# Schema_Proiect_v120.net
KiCad netlist of a schematic drawn in EAGLE
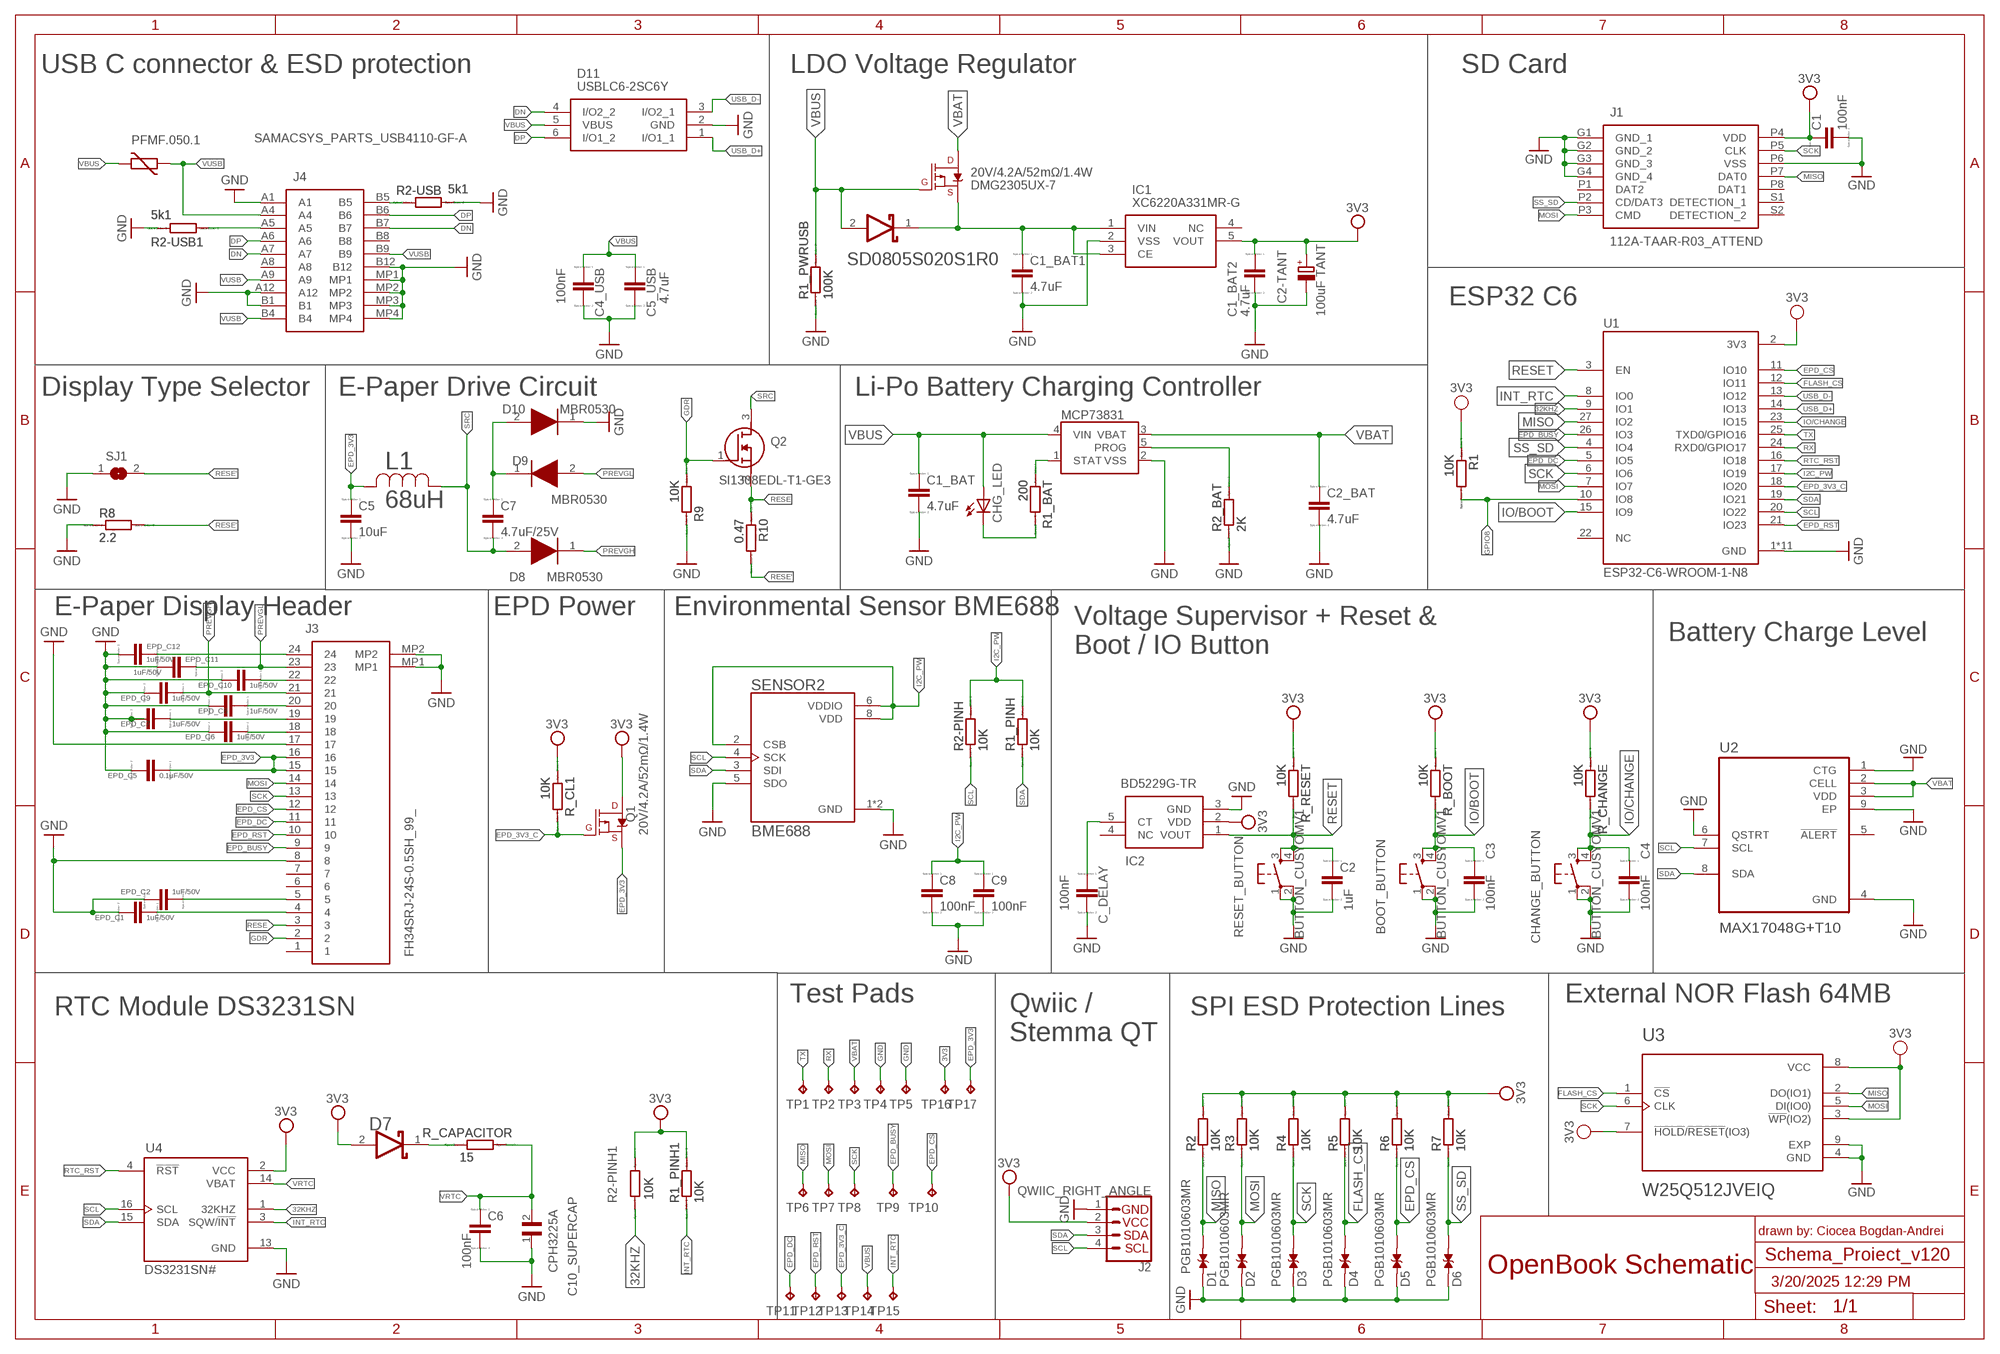
[diagram p0: schematic, sheet 1]

(export (version "E")
  (design (tool "Eeschema 10.0.6"))
  (components
    (comp (ref "BOOT_BUTTON")
      (value "BUTTON_CUSYOMV1")
      (footprint "eagle-import:MYBUTTON")
      (libsource (lib "eagle-import") (part "BUTTON_CUSYOMV1"))
    )
    (comp (ref "C1")
      (value "100nF")
      (footprint "eagle-import:EAGLE-LTSPICE_C0402")
      (libsource (lib "eagle-import") (part "EAGLE-LTSPICE_CC0402"))
    )
    (comp (ref "C1_BAT")
      (value "4.7uF")
      (footprint "eagle-import:EAGLE-LTSPICE_C0402")
      (libsource (lib "eagle-import") (part "EAGLE-LTSPICE_CC0402"))
    )
    (comp (ref "C1_BAT1")
      (value "4.7uF")
      (footprint "eagle-import:EAGLE-LTSPICE_C0402")
      (libsource (lib "eagle-import") (part "EAGLE-LTSPICE_CC0402"))
    )
    (comp (ref "C1_BAT2")
      (value "4.7uF")
      (footprint "eagle-import:EAGLE-LTSPICE_C0402")
      (libsource (lib "eagle-import") (part "EAGLE-LTSPICE_CC0402"))
    )
    (comp (ref "C2")
      (value "1uF")
      (footprint "eagle-import:EAGLE-LTSPICE_C0402")
      (libsource (lib "eagle-import") (part "EAGLE-LTSPICE_CC0402"))
    )
    (comp (ref "C2-TANT")
      (value "100uF TANT")
      (footprint "eagle-import:RCL_CT3528")
      (libsource (lib "eagle-import") (part "RCL_CPOL-EUCT3528"))
    )
    (comp (ref "C2_BAT")
      (value "4.7uF")
      (footprint "eagle-import:EAGLE-LTSPICE_C0402")
      (libsource (lib "eagle-import") (part "EAGLE-LTSPICE_CC0402"))
    )
    (comp (ref "C3")
      (value "100nF")
      (footprint "eagle-import:EAGLE-LTSPICE_C0402")
      (libsource (lib "eagle-import") (part "EAGLE-LTSPICE_CC0402"))
    )
    (comp (ref "C4")
      (value "100nF")
      (footprint "eagle-import:EAGLE-LTSPICE_C0402")
      (libsource (lib "eagle-import") (part "EAGLE-LTSPICE_CC0402"))
    )
    (comp (ref "C4_USB")
      (value "100nF")
      (footprint "eagle-import:EAGLE-LTSPICE_C0402")
      (libsource (lib "eagle-import") (part "EAGLE-LTSPICE_CC0402"))
    )
    (comp (ref "C5")
      (value "10uF")
      (footprint "eagle-import:EAGLE-LTSPICE_C0402")
      (libsource (lib "eagle-import") (part "EAGLE-LTSPICE_CC0402"))
    )
    (comp (ref "C5_USB")
      (value "4.7uF")
      (footprint "eagle-import:EAGLE-LTSPICE_C0402")
      (libsource (lib "eagle-import") (part "EAGLE-LTSPICE_CC0402"))
    )
    (comp (ref "C6")
      (value "100nF")
      (footprint "eagle-import:EAGLE-LTSPICE_C0402")
      (libsource (lib "eagle-import") (part "EAGLE-LTSPICE_CC0402"))
    )
    (comp (ref "C7")
      (value "4.7uF/25V")
      (footprint "eagle-import:EAGLE-LTSPICE_C0402")
      (libsource (lib "eagle-import") (part "EAGLE-LTSPICE_CC0402"))
    )
    (comp (ref "C8")
      (value "100nF")
      (footprint "eagle-import:EAGLE-LTSPICE_C0402")
      (libsource (lib "eagle-import") (part "EAGLE-LTSPICE_CC0402"))
    )
    (comp (ref "C9")
      (value "100nF")
      (footprint "eagle-import:EAGLE-LTSPICE_C0402")
      (libsource (lib "eagle-import") (part "EAGLE-LTSPICE_CC0402"))
    )
    (comp (ref "C10_SUPERCAP")
      (value "CPH3225A")
      (footprint "eagle-import:CAPCP3225X100N")
      (fields (field (name "MF") "Seiko Instruments"))
      (libsource (lib "eagle-import") (part "CPH3225A"))
    )
    (comp (ref "CHANGE_BUTTON")
      (value "BUTTON_CUSYOMV1")
      (footprint "eagle-import:MYBUTTON")
      (libsource (lib "eagle-import") (part "BUTTON_CUSYOMV1"))
    )
    (comp (ref "CHG_LED")
      (value "ADAFRUIT_LEDCHIP-LED0603")
      (footprint "eagle-import:ADAFRUIT_CHIP-LED0603")
      (libsource (lib "eagle-import") (part "ADAFRUIT_LEDCHIP-LED0603"))
    )
    (comp (ref "C_DELAY")
      (value "100nF")
      (footprint "eagle-import:EAGLE-LTSPICE_C0402")
      (libsource (lib "eagle-import") (part "EAGLE-LTSPICE_CC0402"))
    )
    (comp (ref "D1")
      (value "PGB1010603MR")
      (footprint "eagle-import:DIOC1608X36N")
      (fields (field (name "MF") "Littelfuse Inc."))
      (libsource (lib "eagle-import") (part "PGB1010603MR"))
    )
    (comp (ref "D2")
      (value "PGB1010603MR")
      (footprint "eagle-import:DIOC1608X36N")
      (fields (field (name "MF") "Littelfuse Inc."))
      (libsource (lib "eagle-import") (part "PGB1010603MR"))
    )
    (comp (ref "D3")
      (value "PGB1010603MR")
      (footprint "eagle-import:DIOC1608X36N")
      (fields (field (name "MF") "Littelfuse Inc."))
      (libsource (lib "eagle-import") (part "PGB1010603MR"))
    )
    (comp (ref "D4")
      (value "PGB1010603MR")
      (footprint "eagle-import:DIOC1608X36N")
      (fields (field (name "MF") "Littelfuse Inc."))
      (libsource (lib "eagle-import") (part "PGB1010603MR"))
    )
    (comp (ref "D5")
      (value "PGB1010603MR")
      (footprint "eagle-import:DIOC1608X36N")
      (fields (field (name "MF") "Littelfuse Inc."))
      (libsource (lib "eagle-import") (part "PGB1010603MR"))
    )
    (comp (ref "D6")
      (value "PGB1010603MR")
      (footprint "eagle-import:DIOC1608X36N")
      (fields (field (name "MF") "Littelfuse Inc."))
      (libsource (lib "eagle-import") (part "PGB1010603MR"))
    )
    (comp (ref "D7")
      (value "SD0805S020S1R0")
      (footprint "eagle-import:ESP32_WROVER_AVX---SD0805S020S1R0_AVX_SD0805S020S1R0_0")
      (fields
        (field (name "DIGIKEY_PART_NUMBER") "478-7800-1-ND")
        (field (name "MF") "AVX")
        (field (name "MOUSER_PART_NUMBER") "581-SD0805S020S1R0")
      )
      (libsource (lib "eagle-import") (part "ESP32_WROVER_AVX---SD0805S020S1R0_AVX_SD0805S020S1R0_0_0AVX_SD0805S020S1R0_0_0"))
    )
    (comp (ref "D8")
      (value "MBR0530")
      (footprint "eagle-import:SOD3716X135N")
      (fields (field (name "MF") "ON Semiconductor"))
      (libsource (lib "eagle-import") (part "MBR0530"))
    )
    (comp (ref "D9")
      (value "MBR0530")
      (footprint "eagle-import:SOD3716X135N")
      (fields (field (name "MF") "ON Semiconductor"))
      (libsource (lib "eagle-import") (part "MBR0530"))
    )
    (comp (ref "D10")
      (value "MBR0530")
      (footprint "eagle-import:SOD3716X135N")
      (fields (field (name "MF") "ON Semiconductor"))
      (libsource (lib "eagle-import") (part "MBR0530"))
    )
    (comp (ref "D11")
      (value "USBLC6-2SC6Y")
      (footprint "eagle-import:SOT95P280X145-6N")
      (fields (field (name "MF") "STMicroelectronics"))
      (libsource (lib "eagle-import") (part "USBLC6-2SC6Y"))
    )
    (comp (ref "DMG2305UX-7")
      (value "20V/4.2A/52mΩ/1.4W")
      (footprint "eagle-import:ESP32_WROVER_SPARKFUN-DISCRETESEMI_SOT23-3")
      (libsource (lib "eagle-import") (part "ESP32_WROVER_SPARKFUN-DISCRETESEMI_MOSFET_PCH-DMG2305UX-7"))
    )
    (comp (ref "EPD_C1")
      (value "1uF/50V")
      (footprint "eagle-import:EAGLE-LTSPICE_C0402")
      (libsource (lib "eagle-import") (part "EAGLE-LTSPICE_CC0402"))
    )
    (comp (ref "EPD_C2")
      (value "1uF/50V")
      (footprint "eagle-import:EAGLE-LTSPICE_C0402")
      (libsource (lib "eagle-import") (part "EAGLE-LTSPICE_CC0402"))
    )
    (comp (ref "EPD_C5")
      (value "0.1uF/50V")
      (footprint "eagle-import:EAGLE-LTSPICE_C0402")
      (libsource (lib "eagle-import") (part "EAGLE-LTSPICE_CC0402"))
    )
    (comp (ref "EPD_C6")
      (value "1uF/50V")
      (footprint "eagle-import:EAGLE-LTSPICE_C0402")
      (libsource (lib "eagle-import") (part "EAGLE-LTSPICE_CC0402"))
    )
    (comp (ref "EPD_C7")
      (value "1uF/50V")
      (footprint "eagle-import:EAGLE-LTSPICE_C0402")
      (libsource (lib "eagle-import") (part "EAGLE-LTSPICE_CC0402"))
    )
    (comp (ref "EPD_C8")
      (value "1uF/50V")
      (footprint "eagle-import:EAGLE-LTSPICE_C0402")
      (libsource (lib "eagle-import") (part "EAGLE-LTSPICE_CC0402"))
    )
    (comp (ref "EPD_C9")
      (value "1uF/50V")
      (footprint "eagle-import:EAGLE-LTSPICE_C0402")
      (libsource (lib "eagle-import") (part "EAGLE-LTSPICE_CC0402"))
    )
    (comp (ref "EPD_C10")
      (value "1uF/50V")
      (footprint "eagle-import:EAGLE-LTSPICE_C0402")
      (libsource (lib "eagle-import") (part "EAGLE-LTSPICE_CC0402"))
    )
    (comp (ref "EPD_C11")
      (value "1uF/50V")
      (footprint "eagle-import:EAGLE-LTSPICE_C0402")
      (libsource (lib "eagle-import") (part "EAGLE-LTSPICE_CC0402"))
    )
    (comp (ref "EPD_C12")
      (value "1uF/50V")
      (footprint "eagle-import:EAGLE-LTSPICE_C0402")
      (libsource (lib "eagle-import") (part "EAGLE-LTSPICE_CC0402"))
    )
    (comp (ref "IC1")
      (value "XC6220A331MR-G")
      (footprint "eagle-import:SOT95P280X120-5N")
      (fields (field (name "MOUSER_PART_NUMBER") "865-XC6220A331MR-G"))
      (libsource (lib "eagle-import") (part "XC6220A331MR-G"))
    )
    (comp (ref "IC2")
      (value "BD5229G-TR")
      (footprint "eagle-import:SOT95P280X125-5N")
      (fields (field (name "MOUSER_PART_NUMBER") "755-BD5229G-TR"))
      (libsource (lib "eagle-import") (part "BD5229G-TR"))
    )
    (comp (ref "J1")
      (value "112A-TAAR-R03_ATTEND")
      (footprint "eagle-import:112ATAARR03ATTEND")
      (fields (field (name "MANUFACTURER_PART_NUMBER") "112A-TAAR-R03 ATTEND"))
      (libsource (lib "eagle-import") (part "112A-TAAR-R03_ATTEND"))
    )
    (comp (ref "J2")
      (value "QWIIC_RIGHT_ANGLE")
      (footprint "eagle-import:JST04_1MM_RA")
      (libsource (lib "eagle-import") (part "QWIIC_CONNECTORJS-1MM"))
    )
    (comp (ref "J3")
      (value "FH34SRJ-24S-0.5SH_99_")
      (footprint "eagle-import:FH34SRJ24S05SH99")
      (fields
        (field (name "MANUFACTURER_PART_NUMBER") "FH34SRJ-24S-0.5SH(99)")
        (field (name "MOUSER_PART_NUMBER") "798-FH34SRJ24S05SH99")
      )
      (libsource (lib "eagle-import") (part "FH34SRJ-24S-0.5SH_99_"))
    )
    (comp (ref "J4")
      (value "SAMACSYS_PARTS_USB4110-GF-A")
      (footprint "eagle-import:SAMACSYS_PARTS_USB4110GFA")
      (fields
        (field (name "MANUFACTURER_PART_NUMBER") "USB4110-GF-A")
        (field (name "MOUSER_PART_NUMBER") "640-USB4110-GF-A")
      )
      (libsource (lib "eagle-import") (part "SAMACSYS_PARTS_USB4110-GF-A"))
    )
    (comp (ref "L1")
      (value "68uH")
      (footprint "eagle-import:IND_4828-WE-TPC_WRE")
      (fields
        (field (name "MANUFACTURER_PART_NUMBER") "744043680")
        (field (name "COPYRIGHT") "Copyright (C) 2024 Ultra Librarian. All rights reserved.")
      )
      (libsource (lib "eagle-import") (part "744043680IND_4828-WE-TPC_WRE"))
    )
    (comp (ref "MCP73831")
      (value "ESP32_WROVER_SPARKFUN-IC-POWER_MCP73831")
      (footprint "eagle-import:ESP32_WROVER_SPARKFUN-IC-POWER_SOT23-5")
      (libsource (lib "eagle-import") (part "ESP32_WROVER_SPARKFUN-IC-POWER_MCP73831"))
    )
    (comp (ref "PFMF.050.1")
      (value "ESP32C6_VARISTORCN1812")
      (footprint "eagle-import:ESP32C6_VARISTOR_CT_CN1812")
      (libsource (lib "eagle-import") (part "ESP32C6_VARISTORCN1812"))
    )
    (comp (ref "Q1")
      (value "20V/4.2A/52mΩ/1.4W")
      (footprint "eagle-import:ESP32_WROVER_SPARKFUN-DISCRETESEMI_SOT23-3")
      (libsource (lib "eagle-import") (part "ESP32_WROVER_SPARKFUN-DISCRETESEMI_MOSFET_PCH-DMG2305UX-7"))
    )
    (comp (ref "Q2")
      (value "SI1308EDL-T1-GE3")
      (footprint "eagle-import:SOT65P210X110-3N")
      (fields (field (name "MF") "Vishay Siliconix"))
      (libsource (lib "eagle-import") (part "SI1308EDL-T1-GE3"))
    )
    (comp (ref "R1")
      (value "10K")
      (footprint "eagle-import:ESP32_WROVER_EAGLE-LTSPICE_R0402")
      (libsource (lib "eagle-import") (part "ESP32_WROVER_EAGLE-LTSPICE_RR0402"))
    )
    (comp (ref "R1_BAT")
      (value "200")
      (footprint "eagle-import:ESP32_WROVER_EAGLE-LTSPICE_R0402")
      (libsource (lib "eagle-import") (part "ESP32_WROVER_EAGLE-LTSPICE_RR0402"))
    )
    (comp (ref "R1_PINH")
      (value "10K")
      (footprint "eagle-import:ESP32_WROVER_EAGLE-LTSPICE_R0402")
      (libsource (lib "eagle-import") (part "ESP32_WROVER_EAGLE-LTSPICE_RR0402"))
    )
    (comp (ref "R1_PINH1")
      (value "10K")
      (footprint "eagle-import:ESP32_WROVER_EAGLE-LTSPICE_R0402")
      (libsource (lib "eagle-import") (part "ESP32_WROVER_EAGLE-LTSPICE_RR0402"))
    )
    (comp (ref "R1_PWRUSB")
      (value "100K")
      (footprint "eagle-import:ESP32_WROVER_EAGLE-LTSPICE_R0402")
      (libsource (lib "eagle-import") (part "ESP32_WROVER_EAGLE-LTSPICE_RR0402"))
    )
    (comp (ref "R2")
      (value "10K")
      (footprint "eagle-import:ESP32_WROVER_EAGLE-LTSPICE_R0402")
      (libsource (lib "eagle-import") (part "ESP32_WROVER_EAGLE-LTSPICE_RR0402"))
    )
    (comp (ref "R2-PINH")
      (value "10K")
      (footprint "eagle-import:ESP32_WROVER_EAGLE-LTSPICE_R0402")
      (libsource (lib "eagle-import") (part "ESP32_WROVER_EAGLE-LTSPICE_RR0402"))
    )
    (comp (ref "R2-PINH1")
      (value "10K")
      (footprint "eagle-import:ESP32_WROVER_EAGLE-LTSPICE_R0402")
      (libsource (lib "eagle-import") (part "ESP32_WROVER_EAGLE-LTSPICE_RR0402"))
    )
    (comp (ref "R2-USB")
      (value "5k1")
      (footprint "eagle-import:ESP32_WROVER_EAGLE-LTSPICE_R0402")
      (libsource (lib "eagle-import") (part "ESP32_WROVER_EAGLE-LTSPICE_RR0402"))
    )
    (comp (ref "R2-USB1")
      (value "5k1")
      (footprint "eagle-import:ESP32_WROVER_EAGLE-LTSPICE_R0402")
      (libsource (lib "eagle-import") (part "ESP32_WROVER_EAGLE-LTSPICE_RR0402"))
    )
    (comp (ref "R2_BAT")
      (value "2K")
      (footprint "eagle-import:ESP32_WROVER_EAGLE-LTSPICE_R0402")
      (libsource (lib "eagle-import") (part "ESP32_WROVER_EAGLE-LTSPICE_RR0402"))
    )
    (comp (ref "R3")
      (value "10K")
      (footprint "eagle-import:ESP32_WROVER_EAGLE-LTSPICE_R0402")
      (libsource (lib "eagle-import") (part "ESP32_WROVER_EAGLE-LTSPICE_RR0402"))
    )
    (comp (ref "R4")
      (value "10K")
      (footprint "eagle-import:ESP32_WROVER_EAGLE-LTSPICE_R0402")
      (libsource (lib "eagle-import") (part "ESP32_WROVER_EAGLE-LTSPICE_RR0402"))
    )
    (comp (ref "R5")
      (value "10K")
      (footprint "eagle-import:ESP32_WROVER_EAGLE-LTSPICE_R0402")
      (libsource (lib "eagle-import") (part "ESP32_WROVER_EAGLE-LTSPICE_RR0402"))
    )
    (comp (ref "R6")
      (value "10K")
      (footprint "eagle-import:ESP32_WROVER_EAGLE-LTSPICE_R0402")
      (libsource (lib "eagle-import") (part "ESP32_WROVER_EAGLE-LTSPICE_RR0402"))
    )
    (comp (ref "R7")
      (value "10K")
      (footprint "eagle-import:ESP32_WROVER_EAGLE-LTSPICE_R0402")
      (libsource (lib "eagle-import") (part "ESP32_WROVER_EAGLE-LTSPICE_RR0402"))
    )
    (comp (ref "R8")
      (value "2.2")
      (footprint "eagle-import:ESP32_WROVER_EAGLE-LTSPICE_R0402")
      (libsource (lib "eagle-import") (part "ESP32_WROVER_EAGLE-LTSPICE_RR0402"))
    )
    (comp (ref "R9")
      (value "10K")
      (footprint "eagle-import:ESP32_WROVER_EAGLE-LTSPICE_R0402")
      (libsource (lib "eagle-import") (part "ESP32_WROVER_EAGLE-LTSPICE_RR0402"))
    )
    (comp (ref "R10")
      (value "0.47")
      (footprint "eagle-import:ESP32_WROVER_EAGLE-LTSPICE_R0402")
      (libsource (lib "eagle-import") (part "ESP32_WROVER_EAGLE-LTSPICE_RR0402"))
    )
    (comp (ref "RESET_BUTTON")
      (value "BUTTON_CUSYOMV1")
      (footprint "eagle-import:MYBUTTON")
      (libsource (lib "eagle-import") (part "BUTTON_CUSYOMV1"))
    )
    (comp (ref "R_BOOT")
      (value "10K")
      (footprint "eagle-import:ESP32_WROVER_EAGLE-LTSPICE_R0402")
      (libsource (lib "eagle-import") (part "ESP32_WROVER_EAGLE-LTSPICE_RR0402"))
    )
    (comp (ref "R_CAPACITOR")
      (value "15")
      (footprint "eagle-import:ESP32_WROVER_EAGLE-LTSPICE_R0402")
      (libsource (lib "eagle-import") (part "ESP32_WROVER_EAGLE-LTSPICE_RR0402"))
    )
    (comp (ref "R_CHANGE")
      (value "10K")
      (footprint "eagle-import:ESP32_WROVER_EAGLE-LTSPICE_R0402")
      (libsource (lib "eagle-import") (part "ESP32_WROVER_EAGLE-LTSPICE_RR0402"))
    )
    (comp (ref "R_CL1")
      (value "10K")
      (footprint "eagle-import:ESP32_WROVER_EAGLE-LTSPICE_R0402")
      (libsource (lib "eagle-import") (part "ESP32_WROVER_EAGLE-LTSPICE_RR0402"))
    )
    (comp (ref "R_RESET")
      (value "10K")
      (footprint "eagle-import:ESP32_WROVER_EAGLE-LTSPICE_R0402")
      (libsource (lib "eagle-import") (part "ESP32_WROVER_EAGLE-LTSPICE_RR0402"))
    )
    (comp (ref "SD0805S020S1R0")
      (value "ESP32_WROVER_AVX---SD0805S020S1R0_AVX_SD0805S020S1R0_0_0AVX_SD0805S020S1R0_0_0")
      (footprint "eagle-import:ESP32_WROVER_AVX---SD0805S020S1R0_AVX_SD0805S020S1R0_0")
      (fields
        (field (name "DIGIKEY_PART_NUMBER") "478-7800-1-ND")
        (field (name "MF") "AVX")
        (field (name "MOUSER_PART_NUMBER") "581-SD0805S020S1R0")
      )
      (libsource (lib "eagle-import") (part "ESP32_WROVER_AVX---SD0805S020S1R0_AVX_SD0805S020S1R0_0_0AVX_SD0805S020S1R0_0_0"))
    )
    (comp (ref "SENSOR2")
      (value "BME688")
      (footprint "eagle-import:ESP32_WROVER_BME680_PSON80P300X300X100-8N")
      (fields (field (name "MF") "Bosch Sensortec") (field (name "MP") "BME680"))
      (libsource (lib "eagle-import") (part "ESP32_WROVER_BME680_BME680"))
    )
    (comp (ref "SJ1") (value "SJ") (footprint "eagle-import:SJ") (libsource (lib "eagle-import") (part "SJ")))
    (comp (ref "TP1")
      (value "TX")
      (footprint "eagle-import:TP20R")
      (libsource (lib "eagle-import") (part "TPTP20R"))
    )
    (comp (ref "TP2")
      (value "RX")
      (footprint "eagle-import:TP20R")
      (libsource (lib "eagle-import") (part "TPTP20R"))
    )
    (comp (ref "TP3")
      (value "VBAT")
      (footprint "eagle-import:TP20R")
      (libsource (lib "eagle-import") (part "TPTP20R"))
    )
    (comp (ref "TP4")
      (value "GND")
      (footprint "eagle-import:TP20R")
      (libsource (lib "eagle-import") (part "TPTP20R"))
    )
    (comp (ref "TP5")
      (value "GND")
      (footprint "eagle-import:TP20R")
      (libsource (lib "eagle-import") (part "TPTP20R"))
    )
    (comp (ref "TP6")
      (value "MISO")
      (footprint "eagle-import:TP20R")
      (libsource (lib "eagle-import") (part "TPTP20R"))
    )
    (comp (ref "TP7")
      (value "MOSI")
      (footprint "eagle-import:TP20R")
      (libsource (lib "eagle-import") (part "TPTP20R"))
    )
    (comp (ref "TP8")
      (value "SCK")
      (footprint "eagle-import:TP20R")
      (libsource (lib "eagle-import") (part "TPTP20R"))
    )
    (comp (ref "TP9")
      (value "EPD_BUSY")
      (footprint "eagle-import:TP20R")
      (libsource (lib "eagle-import") (part "TPTP20R"))
    )
    (comp (ref "TP10")
      (value "EPD_CS")
      (footprint "eagle-import:TP20R")
      (libsource (lib "eagle-import") (part "TPTP20R"))
    )
    (comp (ref "TP11")
      (value "EPD_DC")
      (footprint "eagle-import:TP20R")
      (libsource (lib "eagle-import") (part "TPTP20R"))
    )
    (comp (ref "TP12")
      (value "EPD_RST")
      (footprint "eagle-import:TP20R")
      (libsource (lib "eagle-import") (part "TPTP20R"))
    )
    (comp (ref "TP13")
      (value "EPD_3V3_C")
      (footprint "eagle-import:TP20R")
      (libsource (lib "eagle-import") (part "TPTP20R"))
    )
    (comp (ref "TP14")
      (value "VBUS")
      (footprint "eagle-import:TP20R")
      (libsource (lib "eagle-import") (part "TPTP20R"))
    )
    (comp (ref "TP15")
      (value "INT_RTC")
      (footprint "eagle-import:TP20R")
      (libsource (lib "eagle-import") (part "TPTP20R"))
    )
    (comp (ref "TP16")
      (value "3V3")
      (footprint "eagle-import:TP20R")
      (libsource (lib "eagle-import") (part "TPTP20R"))
    )
    (comp (ref "TP17")
      (value "EPD_3V3")
      (footprint "eagle-import:TP20R")
      (libsource (lib "eagle-import") (part "TPTP20R"))
    )
    (comp (ref "U1")
      (value "ESP32-C6-WROOM-1-N8")
      (footprint "eagle-import:XCVR_ESP32-C6-WROOM-1-N8")
      (fields (field (name "MF") "Espressif Systems"))
      (libsource (lib "eagle-import") (part "ESP32-C6-WROOM-1-N8"))
    )
    (comp (ref "U2")
      (value "MAX17048G+T10")
      (footprint "eagle-import:SON50P200X200X80-9N")
      (fields (field (name "MF") "Analog Devices"))
      (libsource (lib "eagle-import") (part "MAX17048G+T10"))
    )
    (comp (ref "U3")
      (value "W25Q512JVEIQ")
      (footprint "eagle-import:SON127P600X800X80-9N")
      (fields (field (name "MF") "Winbond Electronics"))
      (libsource (lib "eagle-import") (part "W25Q512JVEIQ"))
    )
    (comp (ref "U4")
      (value "DS3231SN#")
      (footprint "eagle-import:SOIC127P1032X265-16N")
      (fields (field (name "MF") "Analog Devices"))
      (libsource (lib "eagle-import") (part "DS3231SN#"))
    )
  )
  (nets
    (net (code "1") (name "3V3") (class "Default")
      (node (ref "C1") (pin "1") (pinfunction "1_1") (pintype "passive"))
      (node (ref "C1_BAT2") (pin "1") (pinfunction "1_1") (pintype "passive"))
      (node (ref "C2-TANT") (pin "+") (pinfunction "+_+") (pintype "passive"))
      (node (ref "D7") (pin "2") (pinfunction "ANODE_2") (pintype "bidirectional"))
      (node (ref "IC1") (pin "5") (pinfunction "VOUT_5") (pintype "bidirectional"))
      (node (ref "IC2") (pin "2") (pinfunction "VDD_2") (pintype "bidirectional"))
      (node (ref "J1") (pin "P4") (pinfunction "VDD_P4") (pintype "bidirectional"))
      (node (ref "J2") (pin "2") (pinfunction "2_2") (pintype "power_in"))
      (node (ref "Q1") (pin "3") (pinfunction "D_3") (pintype "bidirectional"))
      (node (ref "R1") (pin "1") (pinfunction "1_1") (pintype "passive"))
      (node (ref "R1_PINH1") (pin "2") (pinfunction "2_2") (pintype "passive"))
      (node (ref "R2") (pin "2") (pinfunction "2_2") (pintype "passive"))
      (node (ref "R2-PINH1") (pin "1") (pinfunction "1_1") (pintype "passive"))
      (node (ref "R3") (pin "2") (pinfunction "2_2") (pintype "passive"))
      (node (ref "R4") (pin "2") (pinfunction "2_2") (pintype "passive"))
      (node (ref "R5") (pin "2") (pinfunction "2_2") (pintype "passive"))
      (node (ref "R6") (pin "2") (pinfunction "2_2") (pintype "passive"))
      (node (ref "R7") (pin "2") (pinfunction "2_2") (pintype "passive"))
      (node (ref "R_BOOT") (pin "1") (pinfunction "1_1") (pintype "passive"))
      (node (ref "R_CHANGE") (pin "1") (pinfunction "1_1") (pintype "passive"))
      (node (ref "R_CL1") (pin "1") (pinfunction "1_1") (pintype "passive"))
      (node (ref "R_RESET") (pin "1") (pinfunction "1_1") (pintype "passive"))
      (node (ref "TP16") (pin "TP") (pinfunction "TP_TP") (pintype "input"))
      (node (ref "U1") (pin "2") (pinfunction "3V3_2") (pintype "power_in"))
      (node (ref "U3") (pin "3") (pinfunction "~{WP}(IO2)_3") (pintype "bidirectional"))
      (node (ref "U3") (pin "7") (pinfunction "~{HOLD}/~{RESET}(IO3)_7") (pintype "bidirectional"))
      (node (ref "U3") (pin "8") (pinfunction "VCC_8") (pintype "power_in"))
      (node (ref "U4") (pin "2") (pinfunction "VCC_2") (pintype "power_in"))
    )
    (net (code "2") (name "32KHZ") (class "Default")
      (node (ref "R2-PINH1") (pin "2") (pinfunction "2_2") (pintype "passive"))
      (node (ref "U1") (pin "9") (pinfunction "IO1_9") (pintype "bidirectional"))
      (node (ref "U4") (pin "1") (pinfunction "32KHZ_1") (pintype "output"))
    )
    (net (code "3") (name "DN") (class "Default")
      (node (ref "D11") (pin "4") (pinfunction "I/O2_2_4") (pintype "bidirectional"))
      (node (ref "J4") (pin "A7") (pinfunction "A7_A7") (pintype "bidirectional"))
      (node (ref "J4") (pin "B7") (pinfunction "B7_B7") (pintype "bidirectional"))
    )
    (net (code "4") (name "DP") (class "Default")
      (node (ref "D11") (pin "6") (pinfunction "I/O1_2_6") (pintype "bidirectional"))
      (node (ref "J4") (pin "A6") (pinfunction "A6_A6") (pintype "bidirectional"))
      (node (ref "J4") (pin "B6") (pinfunction "B6_B6") (pintype "bidirectional"))
    )
    (net (code "5") (name "EPD_3V3") (class "Default")
      (node (ref "C5") (pin "1") (pinfunction "1_1") (pintype "passive"))
      (node (ref "EPD_C5") (pin "1") (pinfunction "1_1") (pintype "passive"))
      (node (ref "J3") (pin "15") (pinfunction "15_15") (pintype "bidirectional"))
      (node (ref "J3") (pin "16") (pinfunction "16_16") (pintype "bidirectional"))
      (node (ref "L1") (pin "2") (pinfunction "2_2") (pintype "passive"))
      (node (ref "Q1") (pin "2") (pinfunction "S_2") (pintype "bidirectional"))
      (node (ref "TP17") (pin "TP") (pinfunction "TP_TP") (pintype "input"))
    )
    (net (code "6") (name "EPD_3V3_C") (class "Default")
      (node (ref "Q1") (pin "1") (pinfunction "G_1") (pintype "bidirectional"))
      (node (ref "R_CL1") (pin "2") (pinfunction "2_2") (pintype "passive"))
      (node (ref "TP13") (pin "TP") (pinfunction "TP_TP") (pintype "input"))
      (node (ref "U1") (pin "18") (pinfunction "IO20_18") (pintype "bidirectional"))
    )
    (net (code "7") (name "EPD_BUSY") (class "Default")
      (node (ref "J3") (pin "9") (pinfunction "9_9") (pintype "bidirectional"))
      (node (ref "TP9") (pin "TP") (pinfunction "TP_TP") (pintype "input"))
      (node (ref "U1") (pin "26") (pinfunction "IO3_26") (pintype "bidirectional"))
    )
    (net (code "8") (name "EPD_CS") (class "Default")
      (node (ref "D5") (pin "2") (pinfunction "2_2") (pintype "passive"))
      (node (ref "J3") (pin "12") (pinfunction "12_12") (pintype "bidirectional"))
      (node (ref "R6") (pin "1") (pinfunction "1_1") (pintype "passive"))
      (node (ref "TP10") (pin "TP") (pinfunction "TP_TP") (pintype "input"))
      (node (ref "U1") (pin "11") (pinfunction "IO10_11") (pintype "bidirectional"))
    )
    (net (code "9") (name "EPD_DC") (class "Default")
      (node (ref "J3") (pin "11") (pinfunction "11_11") (pintype "bidirectional"))
      (node (ref "TP11") (pin "TP") (pinfunction "TP_TP") (pintype "input"))
      (node (ref "U1") (pin "5") (pinfunction "IO5_5") (pintype "bidirectional"))
    )
    (net (code "10") (name "EPD_RST") (class "Default")
      (node (ref "J3") (pin "10") (pinfunction "10_10") (pintype "bidirectional"))
      (node (ref "TP12") (pin "TP") (pinfunction "TP_TP") (pintype "input"))
      (node (ref "U1") (pin "21") (pinfunction "IO23_21") (pintype "bidirectional"))
    )
    (net (code "11") (name "FLASH_CS") (class "Default")
      (node (ref "D4") (pin "2") (pinfunction "2_2") (pintype "passive"))
      (node (ref "R5") (pin "1") (pinfunction "1_1") (pintype "passive"))
      (node (ref "U1") (pin "12") (pinfunction "IO11_12") (pintype "bidirectional"))
      (node (ref "U3") (pin "1") (pinfunction "~{CS}_1") (pintype "input"))
    )
    (net (code "12") (name "GDR") (class "Default")
      (node (ref "J3") (pin "2") (pinfunction "2_2") (pintype "bidirectional"))
      (node (ref "Q2") (pin "1") (pinfunction "G_1") (pintype "bidirectional"))
      (node (ref "R9") (pin "1") (pinfunction "1_1") (pintype "passive"))
    )
    (net (code "13") (name "GND") (class "Default")
      (node (ref "BOOT_BUTTON") (pin "1") (pinfunction "1_1") (pintype "passive"))
      (node (ref "BOOT_BUTTON") (pin "2") (pinfunction "2_2") (pintype "passive"))
      (node (ref "C1") (pin "2") (pinfunction "2_2") (pintype "passive"))
      (node (ref "C10_SUPERCAP") (pin "1") (pinfunction "1_1") (pintype "passive"))
      (node (ref "C1_BAT") (pin "2") (pinfunction "2_2") (pintype "passive"))
      (node (ref "C1_BAT1") (pin "2") (pinfunction "2_2") (pintype "passive"))
      (node (ref "C1_BAT2") (pin "2") (pinfunction "2_2") (pintype "passive"))
      (node (ref "C2") (pin "2") (pinfunction "2_2") (pintype "passive"))
      (node (ref "C2-TANT") (pin "-") (pinfunction "-_-") (pintype "passive"))
      (node (ref "C2_BAT") (pin "2") (pinfunction "2_2") (pintype "passive"))
      (node (ref "C3") (pin "2") (pinfunction "2_2") (pintype "passive"))
      (node (ref "C4") (pin "2") (pinfunction "2_2") (pintype "passive"))
      (node (ref "C4_USB") (pin "2") (pinfunction "2_2") (pintype "passive"))
      (node (ref "C5") (pin "2") (pinfunction "2_2") (pintype "passive"))
      (node (ref "C5_USB") (pin "2") (pinfunction "2_2") (pintype "passive"))
      (node (ref "C6") (pin "2") (pinfunction "2_2") (pintype "passive"))
      (node (ref "C8") (pin "2") (pinfunction "2_2") (pintype "passive"))
      (node (ref "C9") (pin "2") (pinfunction "2_2") (pintype "passive"))
      (node (ref "CHANGE_BUTTON") (pin "1") (pinfunction "1_1") (pintype "passive"))
      (node (ref "CHANGE_BUTTON") (pin "2") (pinfunction "2_2") (pintype "passive"))
      (node (ref "C_DELAY") (pin "2") (pinfunction "2_2") (pintype "passive"))
      (node (ref "D1") (pin "1") (pinfunction "1_1") (pintype "passive"))
      (node (ref "D10") (pin "1") (pinfunction "K_1") (pintype "bidirectional"))
      (node (ref "D11") (pin "2") (pinfunction "GND_2") (pintype "bidirectional"))
      (node (ref "D2") (pin "1") (pinfunction "1_1") (pintype "passive"))
      (node (ref "D3") (pin "1") (pinfunction "1_1") (pintype "passive"))
      (node (ref "D4") (pin "1") (pinfunction "1_1") (pintype "passive"))
      (node (ref "D5") (pin "1") (pinfunction "1_1") (pintype "passive"))
      (node (ref "D6") (pin "1") (pinfunction "1_1") (pintype "passive"))
      (node (ref "EPD_C1") (pin "2") (pinfunction "2_2") (pintype "passive"))
      (node (ref "EPD_C10") (pin "2") (pinfunction "2_2") (pintype "passive"))
      (node (ref "EPD_C11") (pin "2") (pinfunction "2_2") (pintype "passive"))
      (node (ref "EPD_C12") (pin "2") (pinfunction "2_2") (pintype "passive"))
      (node (ref "EPD_C2") (pin "2") (pinfunction "2_2") (pintype "passive"))
      (node (ref "EPD_C5") (pin "2") (pinfunction "2_2") (pintype "passive"))
      (node (ref "EPD_C6") (pin "2") (pinfunction "2_2") (pintype "passive"))
      (node (ref "EPD_C7") (pin "2") (pinfunction "2_2") (pintype "passive"))
      (node (ref "EPD_C8") (pin "2") (pinfunction "2_2") (pintype "passive"))
      (node (ref "EPD_C9") (pin "2") (pinfunction "2_2") (pintype "passive"))
      (node (ref "IC1") (pin "2") (pinfunction "VSS_2") (pintype "bidirectional"))
      (node (ref "IC2") (pin "3") (pinfunction "GND_3") (pintype "bidirectional"))
      (node (ref "J1") (pin "G1") (pinfunction "GND_1_G1") (pintype "bidirectional"))
      (node (ref "J1") (pin "G2") (pinfunction "GND_2_G2") (pintype "bidirectional"))
      (node (ref "J1") (pin "G3") (pinfunction "GND_3_G3") (pintype "bidirectional"))
      (node (ref "J1") (pin "G4") (pinfunction "GND_4_G4") (pintype "bidirectional"))
      (node (ref "J1") (pin "P6") (pinfunction "VSS_P6") (pintype "bidirectional"))
      (node (ref "J2") (pin "1") (pinfunction "1_1") (pintype "power_in"))
      (node (ref "J3") (pin "17") (pinfunction "17_17") (pintype "bidirectional"))
      (node (ref "J3") (pin "8") (pinfunction "8_8") (pintype "bidirectional"))
      (node (ref "J3") (pin "MP1") (pinfunction "MP1_MP1") (pintype "bidirectional"))
      (node (ref "J3") (pin "MP2") (pinfunction "MP2_MP2") (pintype "bidirectional"))
      (node (ref "J4") (pin "A1") (pinfunction "A1_A1") (pintype "bidirectional"))
      (node (ref "J4") (pin "A12") (pinfunction "A12_A12") (pintype "bidirectional"))
      (node (ref "J4") (pin "B1") (pinfunction "B1_B1") (pintype "bidirectional"))
      (node (ref "J4") (pin "B12") (pinfunction "B12_B12") (pintype "bidirectional"))
      (node (ref "J4") (pin "MP1") (pinfunction "MP1_MP1") (pintype "bidirectional"))
      (node (ref "J4") (pin "MP2") (pinfunction "MP2_MP2") (pintype "bidirectional"))
      (node (ref "J4") (pin "MP3") (pinfunction "MP3_MP3") (pintype "bidirectional"))
      (node (ref "J4") (pin "MP4") (pinfunction "MP4_MP4") (pintype "bidirectional"))
      (node (ref "MCP73831") (pin "2") (pinfunction "VSS_2") (pintype "power_in"))
      (node (ref "R1_PWRUSB") (pin "1") (pinfunction "1_1") (pintype "passive"))
      (node (ref "R2-USB") (pin "2") (pinfunction "2_2") (pintype "passive"))
      (node (ref "R2-USB1") (pin "1") (pinfunction "1_1") (pintype "passive"))
      (node (ref "R2_BAT") (pin "1") (pinfunction "1_1") (pintype "passive"))
      (node (ref "R8") (pin "1") (pinfunction "1_1") (pintype "passive"))
      (node (ref "R9") (pin "2") (pinfunction "2_2") (pintype "passive"))
      (node (ref "RESET_BUTTON") (pin "1") (pinfunction "1_1") (pintype "passive"))
      (node (ref "RESET_BUTTON") (pin "2") (pinfunction "2_2") (pintype "passive"))
      (node (ref "SENSOR2") (pin "1") (pinfunction "GND_1") (pintype "power_in"))
      (node (ref "SENSOR2") (pin "5") (pinfunction "SDO_5") (pintype "bidirectional"))
      (node (ref "SENSOR2") (pin "7") (pinfunction "GND_7") (pintype "power_in"))
      (node (ref "SJ1") (pin "1") (pinfunction "1_1") (pintype "passive"))
      (node (ref "TP4") (pin "TP") (pinfunction "TP_TP") (pintype "input"))
      (node (ref "TP5") (pin "TP") (pinfunction "TP_TP") (pintype "input"))
      (node (ref "U1") (pin "1") (pinfunction "GND_1") (pintype "power_in"))
      (node (ref "U1") (pin "28") (pinfunction "GND_28") (pintype "power_in"))
      (node (ref "U1") (pin "29_1") (pinfunction "GND_29_1") (pintype "power_in"))
      (node (ref "U1") (pin "29_2") (pinfunction "GND_29_2") (pintype "power_in"))
      (node (ref "U1") (pin "29_3") (pinfunction "GND_29_3") (pintype "power_in"))
      (node (ref "U1") (pin "29_4") (pinfunction "GND_29_4") (pintype "power_in"))
      (node (ref "U1") (pin "29_5") (pinfunction "GND_29_5") (pintype "power_in"))
      (node (ref "U1") (pin "29_6") (pinfunction "GND_29_6") (pintype "power_in"))
      (node (ref "U1") (pin "29_7") (pinfunction "GND_29_7") (pintype "power_in"))
      (node (ref "U1") (pin "29_8") (pinfunction "GND_29_8") (pintype "power_in"))
      (node (ref "U1") (pin "29_9") (pinfunction "GND_29_9") (pintype "power_in"))
      (node (ref "U2") (pin "1") (pinfunction "CTG_1") (pintype "power_in"))
      (node (ref "U2") (pin "4") (pinfunction "GND_4") (pintype "power_in"))
      (node (ref "U2") (pin "6") (pinfunction "QSTRT_6") (pintype "input"))
      (node (ref "U2") (pin "9") (pinfunction "EP_9") (pintype "power_in"))
      (node (ref "U3") (pin "4") (pinfunction "GND_4") (pintype "power_in"))
      (node (ref "U3") (pin "9") (pinfunction "EXP_9") (pintype "passive"))
      (node (ref "U4") (pin "13") (pinfunction "GND_13") (pintype "power_in"))
    )
    (net (code "14") (name "GPIO8") (class "Default")
      (node (ref "R1") (pin "2") (pinfunction "2_2") (pintype "passive"))
      (node (ref "U1") (pin "10") (pinfunction "IO8_10") (pintype "bidirectional"))
    )
    (net (code "15") (name "I2C_PW") (class "Default")
      (node (ref "C8") (pin "1") (pinfunction "1_1") (pintype "passive"))
      (node (ref "C9") (pin "1") (pinfunction "1_1") (pintype "passive"))
      (node (ref "R1_PINH") (pin "2") (pinfunction "2_2") (pintype "passive"))
      (node (ref "R2-PINH") (pin "2") (pinfunction "2_2") (pintype "passive"))
      (node (ref "SENSOR2") (pin "2") (pinfunction "CSB_2") (pintype "input"))
      (node (ref "SENSOR2") (pin "6") (pinfunction "VDDIO_6") (pintype "power_in"))
      (node (ref "SENSOR2") (pin "8") (pinfunction "VDD_8") (pintype "power_in"))
      (node (ref "U1") (pin "17") (pinfunction "IO19_17") (pintype "bidirectional"))
    )
    (net (code "16") (name "INT_RTC") (class "Default")
      (node (ref "R1_PINH1") (pin "1") (pinfunction "1_1") (pintype "passive"))
      (node (ref "TP15") (pin "TP") (pinfunction "TP_TP") (pintype "input"))
      (node (ref "U1") (pin "8") (pinfunction "IO0_8") (pintype "bidirectional"))
      (node (ref "U4") (pin "3") (pinfunction "SQW/~{INT}_3") (pintype "output"))
    )
    (net (code "17") (name "IO{slash}BOOT") (class "Default")
      (node (ref "BOOT_BUTTON") (pin "3") (pinfunction "3_3") (pintype "passive"))
      (node (ref "BOOT_BUTTON") (pin "4") (pinfunction "4_4") (pintype "passive"))
      (node (ref "C3") (pin "1") (pinfunction "1_1") (pintype "passive"))
      (node (ref "R_BOOT") (pin "2") (pinfunction "2_2") (pintype "passive"))
      (node (ref "U1") (pin "15") (pinfunction "IO9_15") (pintype "bidirectional"))
    )
    (net (code "18") (name "IO{slash}CHANGE") (class "Default")
      (node (ref "C4") (pin "1") (pinfunction "1_1") (pintype "passive"))
      (node (ref "CHANGE_BUTTON") (pin "3") (pinfunction "3_3") (pintype "passive"))
      (node (ref "CHANGE_BUTTON") (pin "4") (pinfunction "4_4") (pintype "passive"))
      (node (ref "R_CHANGE") (pin "2") (pinfunction "2_2") (pintype "passive"))
      (node (ref "U1") (pin "23") (pinfunction "IO15_23") (pintype "bidirectional"))
    )
    (net (code "19") (name "MISO") (class "Default")
      (node (ref "D1") (pin "2") (pinfunction "2_2") (pintype "passive"))
      (node (ref "J1") (pin "P7") (pinfunction "DAT0_P7") (pintype "bidirectional"))
      (node (ref "R2") (pin "1") (pinfunction "1_1") (pintype "passive"))
      (node (ref "TP6") (pin "TP") (pinfunction "TP_TP") (pintype "input"))
      (node (ref "U1") (pin "27") (pinfunction "IO2_27") (pintype "bidirectional"))
      (node (ref "U3") (pin "2") (pinfunction "DO(IO1)_2") (pintype "bidirectional"))
    )
    (net (code "20") (name "MOSI") (class "Default")
      (node (ref "D2") (pin "2") (pinfunction "2_2") (pintype "passive"))
      (node (ref "J1") (pin "P3") (pinfunction "CMD_P3") (pintype "bidirectional"))
      (node (ref "J3") (pin "14") (pinfunction "14_14") (pintype "bidirectional"))
      (node (ref "R3") (pin "1") (pinfunction "1_1") (pintype "passive"))
      (node (ref "TP7") (pin "TP") (pinfunction "TP_TP") (pintype "input"))
      (node (ref "U1") (pin "7") (pinfunction "IO7_7") (pintype "bidirectional"))
      (node (ref "U3") (pin "5") (pinfunction "DI(IO0)_5") (pintype "bidirectional"))
    )
    (net (code "21") (name "Net-(CHG_LED-PadC)") (class "Default")
      (node (ref "CHG_LED") (pin "C") (pinfunction "C_C") (pintype "passive"))
      (node (ref "R1_BAT") (pin "2") (pinfunction "2_2") (pintype "passive"))
    )
    (net (code "22") (name "Net-(D7-CATHODE)") (class "Default")
      (node (ref "D7") (pin "1") (pinfunction "CATHODE_1") (pintype "bidirectional"))
      (node (ref "R_CAPACITOR") (pin "2") (pinfunction "2_2") (pintype "passive"))
    )
    (net (code "23") (name "Net-(D10-A)") (class "Default")
      (node (ref "C7") (pin "1") (pinfunction "1_1") (pintype "passive"))
      (node (ref "D10") (pin "2") (pinfunction "A_2") (pintype "bidirectional"))
      (node (ref "D9") (pin "1") (pinfunction "K_1") (pintype "bidirectional"))
    )
    (net (code "24") (name "Net-(DMG2305UX-7-S)") (class "Default")
      (node (ref "C1_BAT1") (pin "1") (pinfunction "1_1") (pintype "passive"))
      (node (ref "DMG2305UX-7") (pin "2") (pinfunction "S_2") (pintype "bidirectional"))
      (node (ref "IC1") (pin "1") (pinfunction "VIN_1") (pintype "bidirectional"))
      (node (ref "IC1") (pin "3") (pinfunction "CE_3") (pintype "bidirectional"))
      (node (ref "SD0805S020S1R0") (pin "1") (pinfunction "CATHODE_1") (pintype "bidirectional"))
    )
    (net (code "25") (name "Net-(EPD_C1-Pad1)") (class "Default")
      (node (ref "EPD_C1") (pin "1") (pinfunction "1_1") (pintype "passive"))
      (node (ref "J3") (pin "4") (pinfunction "4_4") (pintype "bidirectional"))
    )
    (net (code "26") (name "Net-(EPD_C2-Pad1)") (class "Default")
      (node (ref "EPD_C2") (pin "1") (pinfunction "1_1") (pintype "passive"))
      (node (ref "J3") (pin "5") (pinfunction "5_5") (pintype "bidirectional"))
    )
    (net (code "27") (name "Net-(EPD_C6-Pad1)") (class "Default")
      (node (ref "EPD_C6") (pin "1") (pinfunction "1_1") (pintype "passive"))
      (node (ref "J3") (pin "18") (pinfunction "18_18") (pintype "bidirectional"))
    )
    (net (code "28") (name "Net-(EPD_C7-Pad1)") (class "Default")
      (node (ref "EPD_C7") (pin "1") (pinfunction "1_1") (pintype "passive"))
      (node (ref "J3") (pin "19") (pinfunction "19_19") (pintype "bidirectional"))
    )
    (net (code "29") (name "Net-(EPD_C8-Pad1)") (class "Default")
      (node (ref "EPD_C8") (pin "1") (pinfunction "1_1") (pintype "passive"))
      (node (ref "J3") (pin "20") (pinfunction "20_20") (pintype "bidirectional"))
    )
    (net (code "30") (name "Net-(EPD_C10-Pad1)") (class "Default")
      (node (ref "EPD_C10") (pin "1") (pinfunction "1_1") (pintype "passive"))
      (node (ref "J3") (pin "22") (pinfunction "22_22") (pintype "bidirectional"))
    )
    (net (code "31") (name "Net-(EPD_C12-Pad1)") (class "Default")
      (node (ref "EPD_C12") (pin "1") (pinfunction "1_1") (pintype "passive"))
      (node (ref "J3") (pin "24") (pinfunction "24_24") (pintype "bidirectional"))
    )
    (net (code "32") (name "Net-(IC2-CT)") (class "Default")
      (node (ref "C_DELAY") (pin "1") (pinfunction "1_1") (pintype "passive"))
      (node (ref "IC2") (pin "5") (pinfunction "CT_5") (pintype "bidirectional"))
    )
    (net (code "33") (name "Net-(J4-PadA5)") (class "Default")
      (node (ref "J4") (pin "A5") (pinfunction "A5_A5") (pintype "bidirectional"))
      (node (ref "R2-USB1") (pin "2") (pinfunction "2_2") (pintype "passive"))
    )
    (net (code "34") (name "Net-(J4-PadB5)") (class "Default")
      (node (ref "J4") (pin "B5") (pinfunction "B5_B5") (pintype "bidirectional"))
      (node (ref "R2-USB") (pin "1") (pinfunction "1_1") (pintype "passive"))
    )
    (net (code "35") (name "Net-(MCP73831-PROG)") (class "Default")
      (node (ref "MCP73831") (pin "5") (pinfunction "PROG_5") (pintype "input"))
      (node (ref "R2_BAT") (pin "2") (pinfunction "2_2") (pintype "passive"))
    )
    (net (code "36") (name "Net-(MCP73831-STAT)") (class "Default")
      (node (ref "MCP73831") (pin "1") (pinfunction "STAT_1") (pintype "output"))
      (node (ref "R1_BAT") (pin "1") (pinfunction "1_1") (pintype "passive"))
    )
    (net (code "37") (name "PREVGH") (class "Default")
      (node (ref "D8") (pin "1") (pinfunction "K_1") (pintype "bidirectional"))
      (node (ref "EPD_C9") (pin "1") (pinfunction "1_1") (pintype "passive"))
      (node (ref "J3") (pin "21") (pinfunction "21_21") (pintype "bidirectional"))
    )
    (net (code "38") (name "PREVGL") (class "Default")
      (node (ref "D9") (pin "2") (pinfunction "A_2") (pintype "bidirectional"))
      (node (ref "EPD_C11") (pin "1") (pinfunction "1_1") (pintype "passive"))
      (node (ref "J3") (pin "23") (pinfunction "23_23") (pintype "bidirectional"))
    )
    (net (code "39") (name "RESE") (class "Default")
      (node (ref "J3") (pin "3") (pinfunction "3_3") (pintype "bidirectional"))
      (node (ref "Q2") (pin "2") (pinfunction "S_2") (pintype "bidirectional"))
      (node (ref "R10") (pin "1") (pinfunction "1_1") (pintype "passive"))
    )
    (net (code "40") (name "RESE'") (class "Default")
      (node (ref "R10") (pin "2") (pinfunction "2_2") (pintype "passive"))
      (node (ref "R8") (pin "2") (pinfunction "2_2") (pintype "passive"))
      (node (ref "SJ1") (pin "2") (pinfunction "2_2") (pintype "passive"))
    )
    (net (code "41") (name "RESET") (class "Default")
      (node (ref "C2") (pin "1") (pinfunction "1_1") (pintype "passive"))
      (node (ref "IC2") (pin "1") (pinfunction "VOUT_1") (pintype "bidirectional"))
      (node (ref "RESET_BUTTON") (pin "3") (pinfunction "3_3") (pintype "passive"))
      (node (ref "RESET_BUTTON") (pin "4") (pinfunction "4_4") (pintype "passive"))
      (node (ref "R_RESET") (pin "2") (pinfunction "2_2") (pintype "passive"))
      (node (ref "U1") (pin "3") (pinfunction "EN_3") (pintype "input"))
    )
    (net (code "42") (name "RTC_RST") (class "Default")
      (node (ref "U1") (pin "16") (pinfunction "IO18_16") (pintype "bidirectional"))
      (node (ref "U4") (pin "4") (pinfunction "~{RST}_4") (pintype "input"))
    )
    (net (code "43") (name "RX") (class "Default")
      (node (ref "TP2") (pin "TP") (pinfunction "TP_TP") (pintype "input"))
      (node (ref "U1") (pin "24") (pinfunction "RXD0/GPIO17_24") (pintype "bidirectional"))
    )
    (net (code "44") (name "SCK") (class "Default")
      (node (ref "D3") (pin "2") (pinfunction "2_2") (pintype "passive"))
      (node (ref "J1") (pin "P5") (pinfunction "CLK_P5") (pintype "bidirectional"))
      (node (ref "J3") (pin "13") (pinfunction "13_13") (pintype "bidirectional"))
      (node (ref "R4") (pin "1") (pinfunction "1_1") (pintype "passive"))
      (node (ref "TP8") (pin "TP") (pinfunction "TP_TP") (pintype "input"))
      (node (ref "U1") (pin "6") (pinfunction "IO6_6") (pintype "bidirectional"))
      (node (ref "U3") (pin "6") (pinfunction "CLK_6") (pintype "input"))
    )
    (net (code "45") (name "SCL") (class "Default")
      (node (ref "J2") (pin "4") (pinfunction "4_4") (pintype "passive"))
      (node (ref "R2-PINH") (pin "1") (pinfunction "1_1") (pintype "passive"))
      (node (ref "SENSOR2") (pin "4") (pinfunction "SCK_4") (pintype "input"))
      (node (ref "U1") (pin "20") (pinfunction "IO22_20") (pintype "bidirectional"))
      (node (ref "U2") (pin "7") (pinfunction "SCL_7") (pintype "input"))
      (node (ref "U4") (pin "16") (pinfunction "SCL_16") (pintype "input"))
    )
    (net (code "46") (name "SDA") (class "Default")
      (node (ref "J2") (pin "3") (pinfunction "3_3") (pintype "passive"))
      (node (ref "R1_PINH") (pin "1") (pinfunction "1_1") (pintype "passive"))
      (node (ref "SENSOR2") (pin "3") (pinfunction "SDI_3") (pintype "bidirectional"))
      (node (ref "U1") (pin "19") (pinfunction "IO21_19") (pintype "bidirectional"))
      (node (ref "U2") (pin "8") (pinfunction "SDA_8") (pintype "bidirectional"))
      (node (ref "U4") (pin "15") (pinfunction "SDA_15") (pintype "bidirectional"))
    )
    (net (code "47") (name "SRC") (class "Default")
      (node (ref "C7") (pin "2") (pinfunction "2_2") (pintype "passive"))
      (node (ref "D8") (pin "2") (pinfunction "A_2") (pintype "bidirectional"))
      (node (ref "L1") (pin "1") (pinfunction "1_1") (pintype "passive"))
      (node (ref "Q2") (pin "3") (pinfunction "D_3") (pintype "bidirectional"))
    )
    (net (code "48") (name "SS_SD") (class "Default")
      (node (ref "D6") (pin "2") (pinfunction "2_2") (pintype "passive"))
      (node (ref "J1") (pin "P2") (pinfunction "CD/DAT3_P2") (pintype "bidirectional"))
      (node (ref "R7") (pin "1") (pinfunction "1_1") (pintype "passive"))
      (node (ref "U1") (pin "4") (pinfunction "IO4_4") (pintype "bidirectional"))
    )
    (net (code "49") (name "TX") (class "Default")
      (node (ref "TP1") (pin "TP") (pinfunction "TP_TP") (pintype "input"))
      (node (ref "U1") (pin "25") (pinfunction "TXD0/GPIO16_25") (pintype "bidirectional"))
    )
    (net (code "50") (name "USB_D+") (class "Default")
      (node (ref "D11") (pin "1") (pinfunction "I/O1_1_1") (pintype "bidirectional"))
      (node (ref "U1") (pin "14") (pinfunction "IO13_14") (pintype "bidirectional"))
    )
    (net (code "51") (name "USB_D-") (class "Default")
      (node (ref "D11") (pin "3") (pinfunction "I/O2_1_3") (pintype "bidirectional"))
      (node (ref "U1") (pin "13") (pinfunction "IO12_13") (pintype "bidirectional"))
    )
    (net (code "52") (name "VBAT") (class "Default")
      (node (ref "C2_BAT") (pin "1") (pinfunction "1_1") (pintype "passive"))
      (node (ref "DMG2305UX-7") (pin "3") (pinfunction "D_3") (pintype "bidirectional"))
      (node (ref "MCP73831") (pin "3") (pinfunction "VBAT_3") (pintype "power_in"))
      (node (ref "TP3") (pin "TP") (pinfunction "TP_TP") (pintype "input"))
      (node (ref "U2") (pin "2") (pinfunction "CELL_2") (pintype "power_in"))
      (node (ref "U2") (pin "3") (pinfunction "VDD_3") (pintype "power_in"))
    )
    (net (code "53") (name "VBUS") (class "Default")
      (node (ref "C1_BAT") (pin "1") (pinfunction "1_1") (pintype "passive"))
      (node (ref "C4_USB") (pin "1") (pinfunction "1_1") (pintype "passive"))
      (node (ref "C5_USB") (pin "1") (pinfunction "1_1") (pintype "passive"))
      (node (ref "CHG_LED") (pin "A") (pinfunction "A_A") (pintype "passive"))
      (node (ref "D11") (pin "5") (pinfunction "VBUS_5") (pintype "bidirectional"))
      (node (ref "DMG2305UX-7") (pin "1") (pinfunction "G_1") (pintype "bidirectional"))
      (node (ref "MCP73831") (pin "4") (pinfunction "VIN_4") (pintype "power_in"))
      (node (ref "PFMF.050.1") (pin "2") (pinfunction "2_2") (pintype "passive"))
      (node (ref "R1_PWRUSB") (pin "2") (pinfunction "2_2") (pintype "passive"))
      (node (ref "SD0805S020S1R0") (pin "2") (pinfunction "ANODE_2") (pintype "bidirectional"))
      (node (ref "TP14") (pin "TP") (pinfunction "TP_TP") (pintype "input"))
    )
    (net (code "54") (name "VRTC") (class "Default")
      (node (ref "C10_SUPERCAP") (pin "2") (pinfunction "2_2") (pintype "passive"))
      (node (ref "C6") (pin "1") (pinfunction "1_1") (pintype "passive"))
      (node (ref "R_CAPACITOR") (pin "1") (pinfunction "1_1") (pintype "passive"))
      (node (ref "U4") (pin "14") (pinfunction "VBAT_14") (pintype "power_in"))
    )
    (net (code "55") (name "VUSB") (class "Default")
      (node (ref "J4") (pin "A4") (pinfunction "A4_A4") (pintype "bidirectional"))
      (node (ref "J4") (pin "A9") (pinfunction "A9_A9") (pintype "bidirectional"))
      (node (ref "J4") (pin "B4") (pinfunction "B4_B4") (pintype "bidirectional"))
      (node (ref "J4") (pin "B9") (pinfunction "B9_B9") (pintype "bidirectional"))
      (node (ref "PFMF.050.1") (pin "1") (pinfunction "1_1") (pintype "passive"))
    )
    (net (code "56") (name "unconnected-(IC1-NC-Pad4)") (class "Default")
      (node (ref "IC1") (pin "4") (pinfunction "NC_4") (pintype "no_connect"))
    )
    (net (code "57") (name "unconnected-(IC2-NC-Pad4)") (class "Default")
      (node (ref "IC2") (pin "4") (pinfunction "NC_4") (pintype "no_connect"))
    )
    (net (code "58") (name "unconnected-(J1-DAT1-PadP8)") (class "Default")
      (node (ref "J1") (pin "P8") (pinfunction "DAT1_P8") (pintype "bidirectional"))
    )
    (net (code "59") (name "unconnected-(J1-DAT2-PadP1)") (class "Default")
      (node (ref "J1") (pin "P1") (pinfunction "DAT2_P1") (pintype "bidirectional"))
    )
    (net (code "60") (name "unconnected-(J1-DETECTION_1-PadS1)") (class "Default")
      (node (ref "J1") (pin "S1") (pinfunction "DETECTION_1_S1") (pintype "bidirectional"))
    )
    (net (code "61") (name "unconnected-(J1-DETECTION_2-PadS2)") (class "Default")
      (node (ref "J1") (pin "S2") (pinfunction "DETECTION_2_S2") (pintype "bidirectional"))
    )
    (net (code "62") (name "unconnected-(J3-Pad1)") (class "Default")
      (node (ref "J3") (pin "1") (pinfunction "1_1") (pintype "bidirectional"))
    )
    (net (code "63") (name "unconnected-(J3-Pad6)") (class "Default")
      (node (ref "J3") (pin "6") (pinfunction "6_6") (pintype "bidirectional"))
    )
    (net (code "64") (name "unconnected-(J3-Pad7)") (class "Default")
      (node (ref "J3") (pin "7") (pinfunction "7_7") (pintype "bidirectional"))
    )
    (net (code "65") (name "unconnected-(J4-PadA8)") (class "Default")
      (node (ref "J4") (pin "A8") (pinfunction "A8_A8") (pintype "bidirectional"))
    )
    (net (code "66") (name "unconnected-(J4-PadB8)") (class "Default")
      (node (ref "J4") (pin "B8") (pinfunction "B8_B8") (pintype "bidirectional"))
    )
    (net (code "67") (name "unconnected-(U1-NC-Pad22)") (class "Default")
      (node (ref "U1") (pin "22") (pinfunction "NC_22") (pintype "no_connect"))
    )
    (net (code "68") (name "unconnected-(U2-~{ALERT}-Pad5)") (class "Default")
      (node (ref "U2") (pin "5") (pinfunction "~{ALERT}_5") (pintype "output"))
    )
  )
)
